# rxm.net
KiCad netlist of a schematic drawn in EAGLE
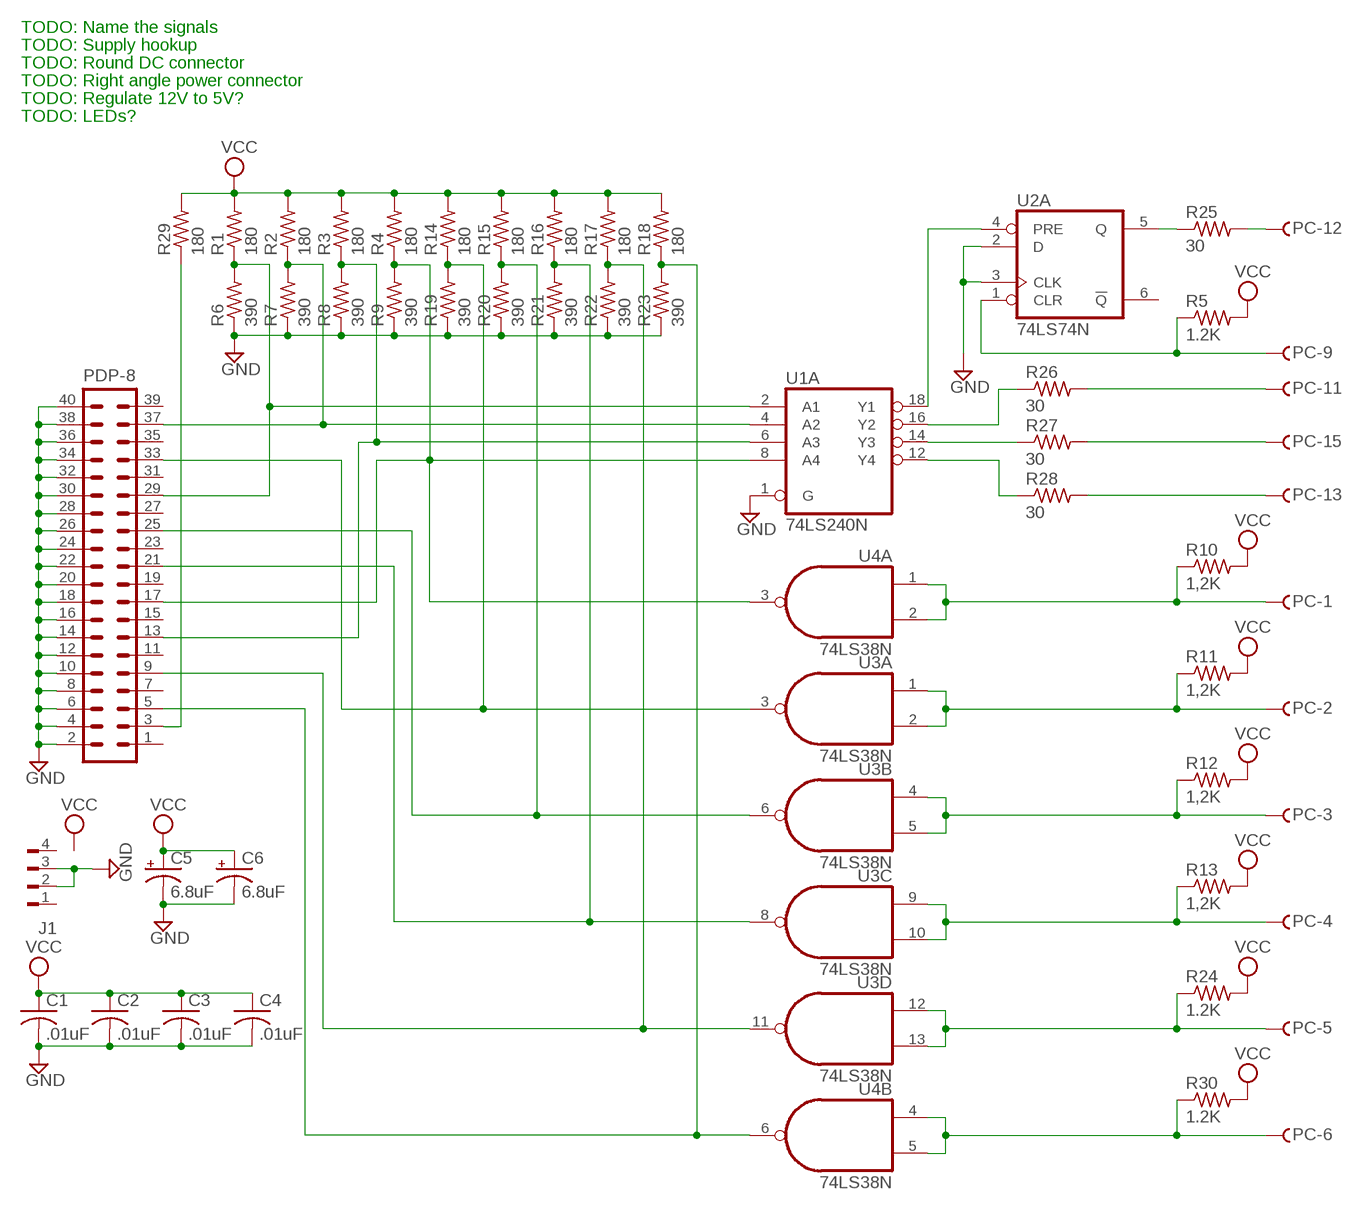
[diagram p0: schematic, sheet 1]

(export (version "E")
  (design (tool "Eeschema 10.0.6"))
  (components
    (comp (ref "C1")
      (value ".01uF")
      (footprint "eagle-import:C050-025X075")
      (libsource (lib "eagle-import") (part "C-US050-025X075"))
    )
    (comp (ref "C2")
      (value ".01uF")
      (footprint "eagle-import:C050-025X075")
      (libsource (lib "eagle-import") (part "C-US050-025X075"))
    )
    (comp (ref "C3")
      (value ".01uF")
      (footprint "eagle-import:C050-025X075")
      (libsource (lib "eagle-import") (part "C-US050-025X075"))
    )
    (comp (ref "C4")
      (value ".01uF")
      (footprint "eagle-import:C050-025X075")
      (libsource (lib "eagle-import") (part "C-US050-025X075"))
    )
    (comp (ref "C5")
      (value "6.8uF")
      (footprint "eagle-import:E2,5-6E")
      (libsource (lib "eagle-import") (part "CPOL-USE2,5-6E"))
    )
    (comp (ref "C6")
      (value "6.8uF")
      (footprint "eagle-import:E2,5-6E")
      (libsource (lib "eagle-import") (part "CPOL-USE2,5-6E"))
    )
    (comp (ref "J1")
      (value "FLOPPY-4")
      (footprint "eagle-import:FLOPPY-4")
      (libsource (lib "eagle-import") (part "FLOPPY-4"))
    )
    (comp (ref "PC")
      (value "F25HS")
      (footprint "eagle-import:F25H")
      (libsource (lib "eagle-import") (part "F25?SH"))
    )
    (comp (ref "PDP-8")
      (value "40H")
      (footprint "eagle-import:40H")
      (libsource (lib "eagle-import") (part "40H"))
    )
    (comp (ref "R1")
      (value "180")
      (footprint "eagle-import:0207_10")
      (libsource (lib "eagle-import") (part "R-US_0207/10"))
    )
    (comp (ref "R2")
      (value "180")
      (footprint "eagle-import:0207_10")
      (libsource (lib "eagle-import") (part "R-US_0207/10"))
    )
    (comp (ref "R3")
      (value "180")
      (footprint "eagle-import:0207_10")
      (libsource (lib "eagle-import") (part "R-US_0207/10"))
    )
    (comp (ref "R4")
      (value "180")
      (footprint "eagle-import:0207_10")
      (libsource (lib "eagle-import") (part "R-US_0207/10"))
    )
    (comp (ref "R5")
      (value "1.2K")
      (footprint "eagle-import:0207_10")
      (libsource (lib "eagle-import") (part "R-US_0207/10"))
    )
    (comp (ref "R6")
      (value "390")
      (footprint "eagle-import:0207_10")
      (libsource (lib "eagle-import") (part "R-US_0207/10"))
    )
    (comp (ref "R7")
      (value "390")
      (footprint "eagle-import:0207_10")
      (libsource (lib "eagle-import") (part "R-US_0207/10"))
    )
    (comp (ref "R8")
      (value "390")
      (footprint "eagle-import:0207_10")
      (libsource (lib "eagle-import") (part "R-US_0207/10"))
    )
    (comp (ref "R9")
      (value "390")
      (footprint "eagle-import:0207_10")
      (libsource (lib "eagle-import") (part "R-US_0207/10"))
    )
    (comp (ref "R10")
      (value "1,2K")
      (footprint "eagle-import:0207_10")
      (libsource (lib "eagle-import") (part "R-US_0207/10"))
    )
    (comp (ref "R11")
      (value "1,2K")
      (footprint "eagle-import:0207_10")
      (libsource (lib "eagle-import") (part "R-US_0207/10"))
    )
    (comp (ref "R12")
      (value "1,2K")
      (footprint "eagle-import:0207_10")
      (libsource (lib "eagle-import") (part "R-US_0207/10"))
    )
    (comp (ref "R13")
      (value "1,2K")
      (footprint "eagle-import:0207_10")
      (libsource (lib "eagle-import") (part "R-US_0207/10"))
    )
    (comp (ref "R14")
      (value "180")
      (footprint "eagle-import:0207_10")
      (libsource (lib "eagle-import") (part "R-US_0207/10"))
    )
    (comp (ref "R15")
      (value "180")
      (footprint "eagle-import:0207_10")
      (libsource (lib "eagle-import") (part "R-US_0207/10"))
    )
    (comp (ref "R16")
      (value "180")
      (footprint "eagle-import:0207_10")
      (libsource (lib "eagle-import") (part "R-US_0207/10"))
    )
    (comp (ref "R17")
      (value "180")
      (footprint "eagle-import:0207_10")
      (libsource (lib "eagle-import") (part "R-US_0207/10"))
    )
    (comp (ref "R18")
      (value "180")
      (footprint "eagle-import:0207_10")
      (libsource (lib "eagle-import") (part "R-US_0207/10"))
    )
    (comp (ref "R19")
      (value "390")
      (footprint "eagle-import:0207_10")
      (libsource (lib "eagle-import") (part "R-US_0207/10"))
    )
    (comp (ref "R20")
      (value "390")
      (footprint "eagle-import:0207_10")
      (libsource (lib "eagle-import") (part "R-US_0207/10"))
    )
    (comp (ref "R21")
      (value "390")
      (footprint "eagle-import:0207_10")
      (libsource (lib "eagle-import") (part "R-US_0207/10"))
    )
    (comp (ref "R22")
      (value "390")
      (footprint "eagle-import:0207_10")
      (libsource (lib "eagle-import") (part "R-US_0207/10"))
    )
    (comp (ref "R23")
      (value "390")
      (footprint "eagle-import:0207_10")
      (libsource (lib "eagle-import") (part "R-US_0207/10"))
    )
    (comp (ref "R24")
      (value "1.2K")
      (footprint "eagle-import:0207_10")
      (libsource (lib "eagle-import") (part "R-US_0207/10"))
    )
    (comp (ref "R25")
      (value "30")
      (footprint "eagle-import:0207_10")
      (libsource (lib "eagle-import") (part "R-US_0207/10"))
    )
    (comp (ref "R26")
      (value "30")
      (footprint "eagle-import:0207_10")
      (libsource (lib "eagle-import") (part "R-US_0207/10"))
    )
    (comp (ref "R27")
      (value "30")
      (footprint "eagle-import:0207_10")
      (libsource (lib "eagle-import") (part "R-US_0207/10"))
    )
    (comp (ref "R28")
      (value "30")
      (footprint "eagle-import:0207_10")
      (libsource (lib "eagle-import") (part "R-US_0207/10"))
    )
    (comp (ref "R29")
      (value "180")
      (footprint "eagle-import:0207_10")
      (libsource (lib "eagle-import") (part "R-US_0207/10"))
    )
    (comp (ref "R30")
      (value "1.2K")
      (footprint "eagle-import:0207_10")
      (libsource (lib "eagle-import") (part "R-US_0207/10"))
    )
    (comp (ref "U1")
      (value "74LS240N")
      (footprint "eagle-import:DIL20")
      (libsource (lib "eagle-import") (part "74240NLS"))
    )
    (comp (ref "U2")
      (value "74LS74N")
      (footprint "eagle-import:DIL14")
      (libsource (lib "eagle-import") (part "7474NLS"))
    )
    (comp (ref "U3")
      (value "74LS38N")
      (footprint "eagle-import:DIL14")
      (libsource (lib "eagle-import") (part "7438NLS"))
    )
    (comp (ref "U4")
      (value "74LS38N")
      (footprint "eagle-import:DIL14")
      (libsource (lib "eagle-import") (part "7438NLS"))
    )
  )
  (nets
    (net (code "1") (name "GND") (class "Default")
      (node (ref "C1") (pin "2") (pinfunction "2_2") (pintype "passive"))
      (node (ref "C2") (pin "2") (pinfunction "2_2") (pintype "passive"))
      (node (ref "C3") (pin "2") (pinfunction "2_2") (pintype "passive"))
      (node (ref "C4") (pin "2") (pinfunction "2_2") (pintype "passive"))
      (node (ref "C5") (pin "-") (pinfunction "-_-") (pintype "passive"))
      (node (ref "C6") (pin "-") (pinfunction "-_-") (pintype "passive"))
      (node (ref "J1") (pin "2") (pinfunction "2_2") (pintype "passive"))
      (node (ref "J1") (pin "3") (pinfunction "3_3") (pintype "passive"))
      (node (ref "PDP-8") (pin "10") (pinfunction "10_10") (pintype "passive"))
      (node (ref "PDP-8") (pin "12") (pinfunction "12_12") (pintype "passive"))
      (node (ref "PDP-8") (pin "14") (pinfunction "14_14") (pintype "passive"))
      (node (ref "PDP-8") (pin "16") (pinfunction "16_16") (pintype "passive"))
      (node (ref "PDP-8") (pin "18") (pinfunction "18_18") (pintype "passive"))
      (node (ref "PDP-8") (pin "2") (pinfunction "2_2") (pintype "passive"))
      (node (ref "PDP-8") (pin "20") (pinfunction "20_20") (pintype "passive"))
      (node (ref "PDP-8") (pin "22") (pinfunction "22_22") (pintype "passive"))
      (node (ref "PDP-8") (pin "24") (pinfunction "24_24") (pintype "passive"))
      (node (ref "PDP-8") (pin "26") (pinfunction "26_26") (pintype "passive"))
      (node (ref "PDP-8") (pin "28") (pinfunction "28_28") (pintype "passive"))
      (node (ref "PDP-8") (pin "30") (pinfunction "30_30") (pintype "passive"))
      (node (ref "PDP-8") (pin "32") (pinfunction "32_32") (pintype "passive"))
      (node (ref "PDP-8") (pin "34") (pinfunction "34_34") (pintype "passive"))
      (node (ref "PDP-8") (pin "36") (pinfunction "36_36") (pintype "passive"))
      (node (ref "PDP-8") (pin "38") (pinfunction "38_38") (pintype "passive"))
      (node (ref "PDP-8") (pin "4") (pinfunction "4_4") (pintype "passive"))
      (node (ref "PDP-8") (pin "40") (pinfunction "40_40") (pintype "passive"))
      (node (ref "PDP-8") (pin "6") (pinfunction "6_6") (pintype "passive"))
      (node (ref "PDP-8") (pin "8") (pinfunction "8_8") (pintype "passive"))
      (node (ref "R19") (pin "1") (pinfunction "1_1") (pintype "passive"))
      (node (ref "R20") (pin "1") (pinfunction "1_1") (pintype "passive"))
      (node (ref "R21") (pin "1") (pinfunction "1_1") (pintype "passive"))
      (node (ref "R22") (pin "1") (pinfunction "1_1") (pintype "passive"))
      (node (ref "R23") (pin "1") (pinfunction "1_1") (pintype "passive"))
      (node (ref "R6") (pin "1") (pinfunction "1_1") (pintype "passive"))
      (node (ref "R7") (pin "1") (pinfunction "1_1") (pintype "passive"))
      (node (ref "R8") (pin "1") (pinfunction "1_1") (pintype "passive"))
      (node (ref "R9") (pin "1") (pinfunction "1_1") (pintype "passive"))
      (node (ref "U1") (pin "1") (pinfunction "G_1") (pintype "input"))
      (node (ref "U2") (pin "2") (pinfunction "D_2") (pintype "input"))
      (node (ref "U2") (pin "3") (pinfunction "CLK_3") (pintype "input"))
    )
    (net (code "2") (name "Net-(PCA-F)") (class "Default")
      (node (ref "PC") (pin "1") (pinfunction "F_1") (pintype "passive"))
      (node (ref "R10") (pin "1") (pinfunction "1_1") (pintype "passive"))
      (node (ref "U4") (pin "1") (pinfunction "I0_1") (pintype "input"))
      (node (ref "U4") (pin "2") (pinfunction "I1_2") (pintype "input"))
    )
    (net (code "3") (name "Net-(PCC-F)") (class "Default")
      (node (ref "PC") (pin "11") (pinfunction "F_11") (pintype "passive"))
      (node (ref "R26") (pin "2") (pinfunction "2_2") (pintype "passive"))
    )
    (net (code "4") (name "Net-(PCD-F)") (class "Default")
      (node (ref "PC") (pin "12") (pinfunction "F_12") (pintype "passive"))
      (node (ref "R25") (pin "2") (pinfunction "2_2") (pintype "passive"))
    )
    (net (code "5") (name "Net-(PCE-F)") (class "Default")
      (node (ref "PC") (pin "13") (pinfunction "F_13") (pintype "passive"))
      (node (ref "R28") (pin "2") (pinfunction "2_2") (pintype "passive"))
    )
    (net (code "6") (name "Net-(PCG-F)") (class "Default")
      (node (ref "PC") (pin "15") (pinfunction "F_15") (pintype "passive"))
      (node (ref "R27") (pin "2") (pinfunction "2_2") (pintype "passive"))
    )
    (net (code "7") (name "Net-(PCL-F)") (class "Default")
      (node (ref "PC") (pin "2") (pinfunction "F_2") (pintype "passive"))
      (node (ref "R11") (pin "1") (pinfunction "1_1") (pintype "passive"))
      (node (ref "U3") (pin "1") (pinfunction "I0_1") (pintype "input"))
      (node (ref "U3") (pin "2") (pinfunction "I1_2") (pintype "input"))
    )
    (net (code "8") (name "Net-(PCS-F)") (class "Default")
      (node (ref "PC") (pin "3") (pinfunction "F_3") (pintype "passive"))
      (node (ref "R12") (pin "1") (pinfunction "1_1") (pintype "passive"))
      (node (ref "U3") (pin "4") (pinfunction "I0_4") (pintype "input"))
      (node (ref "U3") (pin "5") (pinfunction "I1_5") (pintype "input"))
    )
    (net (code "9") (name "Net-(PCT-F)") (class "Default")
      (node (ref "PC") (pin "4") (pinfunction "F_4") (pintype "passive"))
      (node (ref "R13") (pin "1") (pinfunction "1_1") (pintype "passive"))
      (node (ref "U3") (pin "10") (pinfunction "I1_10") (pintype "input"))
      (node (ref "U3") (pin "9") (pinfunction "I0_9") (pintype "input"))
    )
    (net (code "10") (name "Net-(PCU-F)") (class "Default")
      (node (ref "PC") (pin "5") (pinfunction "F_5") (pintype "passive"))
      (node (ref "R24") (pin "1") (pinfunction "1_1") (pintype "passive"))
      (node (ref "U3") (pin "12") (pinfunction "I0_12") (pintype "input"))
      (node (ref "U3") (pin "13") (pinfunction "I1_13") (pintype "input"))
    )
    (net (code "11") (name "Net-(PCV-F)") (class "Default")
      (node (ref "PC") (pin "6") (pinfunction "F_6") (pintype "passive"))
      (node (ref "R30") (pin "1") (pinfunction "1_1") (pintype "passive"))
      (node (ref "U4") (pin "4") (pinfunction "I0_4") (pintype "input"))
      (node (ref "U4") (pin "5") (pinfunction "I1_5") (pintype "input"))
    )
    (net (code "12") (name "Net-(PCY-F)") (class "Default")
      (node (ref "PC") (pin "9") (pinfunction "F_9") (pintype "passive"))
      (node (ref "R5") (pin "1") (pinfunction "1_1") (pintype "passive"))
      (node (ref "U2") (pin "1") (pinfunction "CLR_1") (pintype "input"))
    )
    (net (code "13") (name "Net-(PDP-8-Pad3)") (class "Default")
      (node (ref "PDP-8") (pin "3") (pinfunction "3_3") (pintype "passive"))
      (node (ref "R29") (pin "1") (pinfunction "1_1") (pintype "passive"))
    )
    (net (code "14") (name "Net-(U1A-A1)") (class "Default")
      (node (ref "PDP-8") (pin "29") (pinfunction "29_29") (pintype "passive"))
      (node (ref "R1") (pin "1") (pinfunction "1_1") (pintype "passive"))
      (node (ref "R6") (pin "2") (pinfunction "2_2") (pintype "passive"))
      (node (ref "U1") (pin "2") (pinfunction "A1_2") (pintype "input"))
    )
    (net (code "15") (name "Net-(U1A-A2)") (class "Default")
      (node (ref "PDP-8") (pin "37") (pinfunction "37_37") (pintype "passive"))
      (node (ref "R2") (pin "1") (pinfunction "1_1") (pintype "passive"))
      (node (ref "R7") (pin "2") (pinfunction "2_2") (pintype "passive"))
      (node (ref "U1") (pin "4") (pinfunction "A2_4") (pintype "input"))
    )
    (net (code "16") (name "Net-(U1A-A3)") (class "Default")
      (node (ref "PDP-8") (pin "13") (pinfunction "13_13") (pintype "passive"))
      (node (ref "R3") (pin "1") (pinfunction "1_1") (pintype "passive"))
      (node (ref "R8") (pin "2") (pinfunction "2_2") (pintype "passive"))
      (node (ref "U1") (pin "6") (pinfunction "A3_6") (pintype "input"))
    )
    (net (code "17") (name "Net-(U1A-A4)") (class "Default")
      (node (ref "PDP-8") (pin "17") (pinfunction "17_17") (pintype "passive"))
      (node (ref "R4") (pin "1") (pinfunction "1_1") (pintype "passive"))
      (node (ref "R9") (pin "2") (pinfunction "2_2") (pintype "passive"))
      (node (ref "U1") (pin "8") (pinfunction "A4_8") (pintype "input"))
      (node (ref "U4") (pin "3") (pinfunction "O_3") (pintype "open_collector"))
    )
    (net (code "18") (name "Net-(U1A-Y1)") (class "Default")
      (node (ref "U1") (pin "18") (pinfunction "Y1_18") (pintype "tri_state"))
      (node (ref "U2") (pin "4") (pinfunction "PRE_4") (pintype "input"))
    )
    (net (code "19") (name "Net-(U1A-Y2)") (class "Default")
      (node (ref "R26") (pin "1") (pinfunction "1_1") (pintype "passive"))
      (node (ref "U1") (pin "16") (pinfunction "Y2_16") (pintype "tri_state"))
    )
    (net (code "20") (name "Net-(U1A-Y3)") (class "Default")
      (node (ref "R27") (pin "1") (pinfunction "1_1") (pintype "passive"))
      (node (ref "U1") (pin "14") (pinfunction "Y3_14") (pintype "tri_state"))
    )
    (net (code "21") (name "Net-(U1A-Y4)") (class "Default")
      (node (ref "R28") (pin "1") (pinfunction "1_1") (pintype "passive"))
      (node (ref "U1") (pin "12") (pinfunction "Y4_12") (pintype "tri_state"))
    )
    (net (code "22") (name "Net-(U2A-Q)") (class "Default")
      (node (ref "R25") (pin "1") (pinfunction "1_1") (pintype "passive"))
      (node (ref "U2") (pin "5") (pinfunction "Q_5") (pintype "output"))
    )
    (net (code "23") (name "Net-(U3A-O)") (class "Default")
      (node (ref "PDP-8") (pin "33") (pinfunction "33_33") (pintype "passive"))
      (node (ref "R14") (pin "1") (pinfunction "1_1") (pintype "passive"))
      (node (ref "R19") (pin "2") (pinfunction "2_2") (pintype "passive"))
      (node (ref "U3") (pin "3") (pinfunction "O_3") (pintype "open_collector"))
    )
    (net (code "24") (name "Net-(U3B-O)") (class "Default")
      (node (ref "PDP-8") (pin "25") (pinfunction "25_25") (pintype "passive"))
      (node (ref "R15") (pin "1") (pinfunction "1_1") (pintype "passive"))
      (node (ref "R20") (pin "2") (pinfunction "2_2") (pintype "passive"))
      (node (ref "U3") (pin "6") (pinfunction "O_6") (pintype "open_collector"))
    )
    (net (code "25") (name "Net-(U3C-O)") (class "Default")
      (node (ref "PDP-8") (pin "21") (pinfunction "21_21") (pintype "passive"))
      (node (ref "R16") (pin "1") (pinfunction "1_1") (pintype "passive"))
      (node (ref "R21") (pin "2") (pinfunction "2_2") (pintype "passive"))
      (node (ref "U3") (pin "8") (pinfunction "O_8") (pintype "open_collector"))
    )
    (net (code "26") (name "Net-(U3D-O)") (class "Default")
      (node (ref "PDP-8") (pin "9") (pinfunction "9_9") (pintype "passive"))
      (node (ref "R17") (pin "1") (pinfunction "1_1") (pintype "passive"))
      (node (ref "R22") (pin "2") (pinfunction "2_2") (pintype "passive"))
      (node (ref "U3") (pin "11") (pinfunction "O_11") (pintype "open_collector"))
    )
    (net (code "27") (name "Net-(U4B-O)") (class "Default")
      (node (ref "PDP-8") (pin "5") (pinfunction "5_5") (pintype "passive"))
      (node (ref "R18") (pin "1") (pinfunction "1_1") (pintype "passive"))
      (node (ref "R23") (pin "2") (pinfunction "2_2") (pintype "passive"))
      (node (ref "U4") (pin "6") (pinfunction "O_6") (pintype "open_collector"))
    )
    (net (code "28") (name "VCC") (class "Default")
      (node (ref "C1") (pin "1") (pinfunction "1_1") (pintype "passive"))
      (node (ref "C2") (pin "1") (pinfunction "1_1") (pintype "passive"))
      (node (ref "C3") (pin "1") (pinfunction "1_1") (pintype "passive"))
      (node (ref "C4") (pin "1") (pinfunction "1_1") (pintype "passive"))
      (node (ref "C5") (pin "+") (pinfunction "+_+") (pintype "passive"))
      (node (ref "C6") (pin "+") (pinfunction "+_+") (pintype "passive"))
      (node (ref "R1") (pin "2") (pinfunction "2_2") (pintype "passive"))
      (node (ref "R10") (pin "2") (pinfunction "2_2") (pintype "passive"))
      (node (ref "R11") (pin "2") (pinfunction "2_2") (pintype "passive"))
      (node (ref "R12") (pin "2") (pinfunction "2_2") (pintype "passive"))
      (node (ref "R13") (pin "2") (pinfunction "2_2") (pintype "passive"))
      (node (ref "R14") (pin "2") (pinfunction "2_2") (pintype "passive"))
      (node (ref "R15") (pin "2") (pinfunction "2_2") (pintype "passive"))
      (node (ref "R16") (pin "2") (pinfunction "2_2") (pintype "passive"))
      (node (ref "R17") (pin "2") (pinfunction "2_2") (pintype "passive"))
      (node (ref "R18") (pin "2") (pinfunction "2_2") (pintype "passive"))
      (node (ref "R2") (pin "2") (pinfunction "2_2") (pintype "passive"))
      (node (ref "R24") (pin "2") (pinfunction "2_2") (pintype "passive"))
      (node (ref "R29") (pin "2") (pinfunction "2_2") (pintype "passive"))
      (node (ref "R3") (pin "2") (pinfunction "2_2") (pintype "passive"))
      (node (ref "R30") (pin "2") (pinfunction "2_2") (pintype "passive"))
      (node (ref "R4") (pin "2") (pinfunction "2_2") (pintype "passive"))
      (node (ref "R5") (pin "2") (pinfunction "2_2") (pintype "passive"))
    )
    (net (code "29") (name "unconnected-(J1-Pad1)") (class "Default")
      (node (ref "J1") (pin "1") (pinfunction "1_1") (pintype "passive"))
    )
    (net (code "30") (name "unconnected-(J1-Pad4)") (class "Default")
      (node (ref "J1") (pin "4") (pinfunction "4_4") (pintype "passive"))
    )
    (net (code "31") (name "unconnected-(PDP-8-Pad1)") (class "Default")
      (node (ref "PDP-8") (pin "1") (pinfunction "1_1") (pintype "passive"))
    )
    (net (code "32") (name "unconnected-(PDP-8-Pad7)") (class "Default")
      (node (ref "PDP-8") (pin "7") (pinfunction "7_7") (pintype "passive"))
    )
    (net (code "33") (name "unconnected-(PDP-8-Pad11)") (class "Default")
      (node (ref "PDP-8") (pin "11") (pinfunction "11_11") (pintype "passive"))
    )
    (net (code "34") (name "unconnected-(PDP-8-Pad15)") (class "Default")
      (node (ref "PDP-8") (pin "15") (pinfunction "15_15") (pintype "passive"))
    )
    (net (code "35") (name "unconnected-(PDP-8-Pad19)") (class "Default")
      (node (ref "PDP-8") (pin "19") (pinfunction "19_19") (pintype "passive"))
    )
    (net (code "36") (name "unconnected-(PDP-8-Pad23)") (class "Default")
      (node (ref "PDP-8") (pin "23") (pinfunction "23_23") (pintype "passive"))
    )
    (net (code "37") (name "unconnected-(PDP-8-Pad27)") (class "Default")
      (node (ref "PDP-8") (pin "27") (pinfunction "27_27") (pintype "passive"))
    )
    (net (code "38") (name "unconnected-(PDP-8-Pad31)") (class "Default")
      (node (ref "PDP-8") (pin "31") (pinfunction "31_31") (pintype "passive"))
    )
    (net (code "39") (name "unconnected-(PDP-8-Pad35)") (class "Default")
      (node (ref "PDP-8") (pin "35") (pinfunction "35_35") (pintype "passive"))
    )
    (net (code "40") (name "unconnected-(PDP-8-Pad39)") (class "Default")
      (node (ref "PDP-8") (pin "39") (pinfunction "39_39") (pintype "passive"))
    )
    (net (code "41") (name "unconnected-(U2A-~{Q}-Pad6)") (class "Default")
      (node (ref "U2") (pin "6") (pinfunction "~{Q}_6") (pintype "output"))
    )
  )
)
